# opto-relay.net
KiCad netlist of a schematic drawn in EAGLE
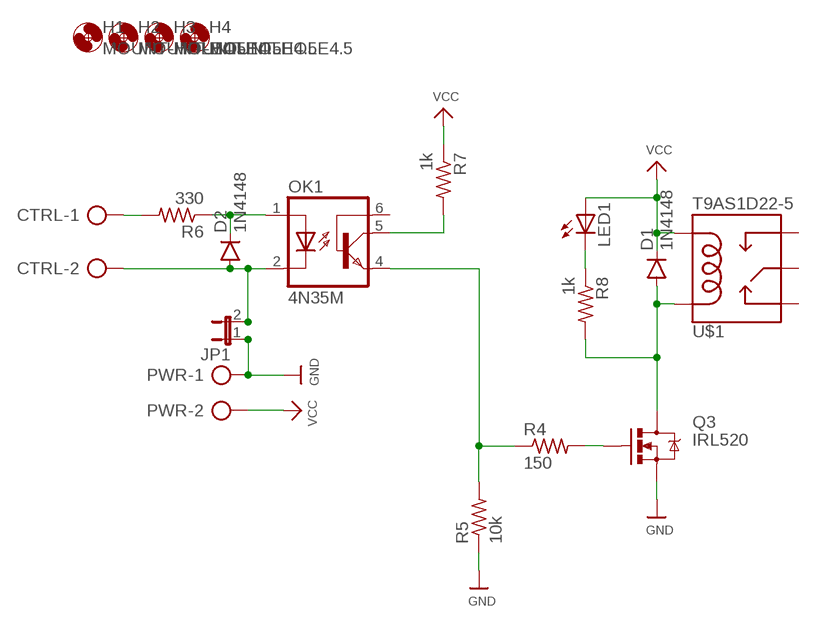
[diagram p0: schematic, sheet 1]

(export (version "E")
  (design (tool "Eeschema 10.0.6"))
  (components
    (comp (ref "CTRL")
      (value "AK500/2")
      (footprint "eagle-import:AK500_2")
      (libsource (lib "eagle-import") (part "AK500/2"))
    )
    (comp (ref "D1")
      (value "1N4148")
      (footprint "eagle-import:DIODE-1N4148")
      (libsource (lib "eagle-import") (part "DIODE1N4148"))
    )
    (comp (ref "D2")
      (value "1N4148")
      (footprint "eagle-import:DIODE-1N4148")
      (libsource (lib "eagle-import") (part "DIODE1N4148"))
    )
    (comp (ref "H1")
      (value "MOUNT-HOLE4.5")
      (footprint "eagle-import:4,5")
      (libsource (lib "eagle-import") (part "MOUNT-HOLE4.5"))
    )
    (comp (ref "H2")
      (value "MOUNT-HOLE4.5")
      (footprint "eagle-import:4,5")
      (libsource (lib "eagle-import") (part "MOUNT-HOLE4.5"))
    )
    (comp (ref "H3")
      (value "MOUNT-HOLE4.5")
      (footprint "eagle-import:4,5")
      (libsource (lib "eagle-import") (part "MOUNT-HOLE4.5"))
    )
    (comp (ref "H4")
      (value "MOUNT-HOLE4.5")
      (footprint "eagle-import:4,5")
      (libsource (lib "eagle-import") (part "MOUNT-HOLE4.5"))
    )
    (comp (ref "JP1")
      (value "JP1E")
      (footprint "eagle-import:JP1")
      (libsource (lib "eagle-import") (part "JP1E"))
    )
    (comp (ref "LED1")
      (value "LED5MM")
      (footprint "eagle-import:LED5MM")
      (libsource (lib "eagle-import") (part "LED5MM"))
    )
    (comp (ref "OK1")
      (value "4N35M")
      (footprint "eagle-import:DIL06")
      (fields (field (name "MPN") "4N35-M"))
      (libsource (lib "eagle-import") (part "4N?M35"))
    )
    (comp (ref "PWR")
      (value "AK500/2")
      (footprint "eagle-import:AK500_2")
      (libsource (lib "eagle-import") (part "AK500/2"))
    )
    (comp (ref "Q3")
      (value "IRL520")
      (footprint "eagle-import:TO220V")
      (libsource (lib "eagle-import") (part "MOSFET-NCHANNELFQP30N06L"))
    )
    (comp (ref "R4")
      (value "150")
      (footprint "eagle-import:0207_10")
      (libsource (lib "eagle-import") (part "R-US_0207/10"))
    )
    (comp (ref "R5")
      (value "10k")
      (footprint "eagle-import:0207_10")
      (libsource (lib "eagle-import") (part "R-US_0207/10"))
    )
    (comp (ref "R6")
      (value "330")
      (footprint "eagle-import:0207_10")
      (libsource (lib "eagle-import") (part "R-US_0207/10"))
    )
    (comp (ref "R7")
      (value "1k")
      (footprint "eagle-import:0207_10")
      (libsource (lib "eagle-import") (part "R-US_0207/10"))
    )
    (comp (ref "R8")
      (value "1k")
      (footprint "eagle-import:0207_10")
      (libsource (lib "eagle-import") (part "R-US_0207/10"))
    )
    (comp (ref "U$1")
      (value "T9AS1D22-5")
      (footprint "eagle-import:RELAY-T9A-2")
      (libsource (lib "eagle-import") (part "RELAYPTH3"))
    )
  )
  (nets
    (net (code "1") (name "GND") (class "Default")
      (node (ref "JP1") (pin "1") (pinfunction "1_1") (pintype "passive"))
      (node (ref "PWR") (pin "1") (pinfunction "KL_1") (pintype "passive"))
      (node (ref "Q3") (pin "3") (pinfunction "S_3") (pintype "passive"))
      (node (ref "R5") (pin "1") (pinfunction "1_1") (pintype "passive"))
    )
    (net (code "2") (name "Net-(CTRLA-KL)") (class "Default")
      (node (ref "CTRL") (pin "1") (pinfunction "KL_1") (pintype "passive"))
      (node (ref "R6") (pin "2") (pinfunction "2_2") (pintype "passive"))
    )
    (net (code "3") (name "Net-(CTRLB-KL)") (class "Default")
      (node (ref "CTRL") (pin "2") (pinfunction "KL_2") (pintype "passive"))
      (node (ref "D2") (pin "A") (pinfunction "A_A") (pintype "passive"))
      (node (ref "JP1") (pin "2") (pinfunction "2_2") (pintype "passive"))
      (node (ref "OK1") (pin "2") (pinfunction "C_2") (pintype "passive"))
    )
    (net (code "4") (name "Net-(LED1-C)") (class "Default")
      (node (ref "LED1") (pin "K") (pinfunction "C_K") (pintype "passive"))
      (node (ref "R8") (pin "1") (pinfunction "1_1") (pintype "passive"))
    )
    (net (code "5") (name "Net-(OK1-A)") (class "Default")
      (node (ref "D2") (pin "C") (pinfunction "C_C") (pintype "passive"))
      (node (ref "OK1") (pin "1") (pinfunction "A_1") (pintype "passive"))
      (node (ref "R6") (pin "1") (pinfunction "1_1") (pintype "passive"))
    )
    (net (code "6") (name "Net-(OK1-COL)") (class "Default")
      (node (ref "OK1") (pin "5") (pinfunction "COL_5") (pintype "passive"))
      (node (ref "R7") (pin "2") (pinfunction "2_2") (pintype "passive"))
    )
    (net (code "7") (name "Net-(OK1-EMI)") (class "Default")
      (node (ref "OK1") (pin "4") (pinfunction "EMI_4") (pintype "passive"))
      (node (ref "R4") (pin "1") (pinfunction "1_1") (pintype "passive"))
      (node (ref "R5") (pin "2") (pinfunction "2_2") (pintype "passive"))
    )
    (net (code "8") (name "Net-(Q3-D)") (class "Default")
      (node (ref "D1") (pin "A") (pinfunction "A_A") (pintype "passive"))
      (node (ref "Q3") (pin "2") (pinfunction "D_2") (pintype "passive"))
      (node (ref "R8") (pin "2") (pinfunction "2_2") (pintype "passive"))
      (node (ref "U$1") (pin "COIL1") (pinfunction "COIL1_COIL1") (pintype "bidirectional"))
    )
    (net (code "9") (name "Net-(Q3-G)") (class "Default")
      (node (ref "Q3") (pin "1") (pinfunction "G_1") (pintype "passive"))
      (node (ref "R4") (pin "2") (pinfunction "2_2") (pintype "passive"))
    )
    (net (code "10") (name "VCC") (class "Default")
      (node (ref "D1") (pin "C") (pinfunction "C_C") (pintype "passive"))
      (node (ref "LED1") (pin "A") (pinfunction "A_A") (pintype "passive"))
      (node (ref "PWR") (pin "2") (pinfunction "KL_2") (pintype "passive"))
      (node (ref "R7") (pin "1") (pinfunction "1_1") (pintype "passive"))
      (node (ref "U$1") (pin "COIL2") (pinfunction "COIL2_COIL2") (pintype "bidirectional"))
    )
    (net (code "11") (name "unconnected-(OK1-BAS-Pad6)") (class "Default")
      (node (ref "OK1") (pin "6") (pinfunction "BAS_6") (pintype "passive"))
    )
    (net (code "12") (name "unconnected-(U$1-PadMAIN)") (class "Default")
      (node (ref "U$1") (pin "MAIN") (pinfunction "MAIN_MAIN") (pintype "bidirectional"))
    )
    (net (code "13") (name "unconnected-(U$1-PadNC)") (class "Default")
      (node (ref "U$1") (pin "NC") (pinfunction "NC_NC") (pintype "bidirectional"))
    )
    (net (code "14") (name "unconnected-(U$1-PadNO)") (class "Default")
      (node (ref "U$1") (pin "NO") (pinfunction "NO_NO") (pintype "bidirectional"))
    )
  )
)
